# ProPrj_LillyPadPro_2025-09-27.net
KiCad netlist of a schematic drawn in EasyEDA Pro
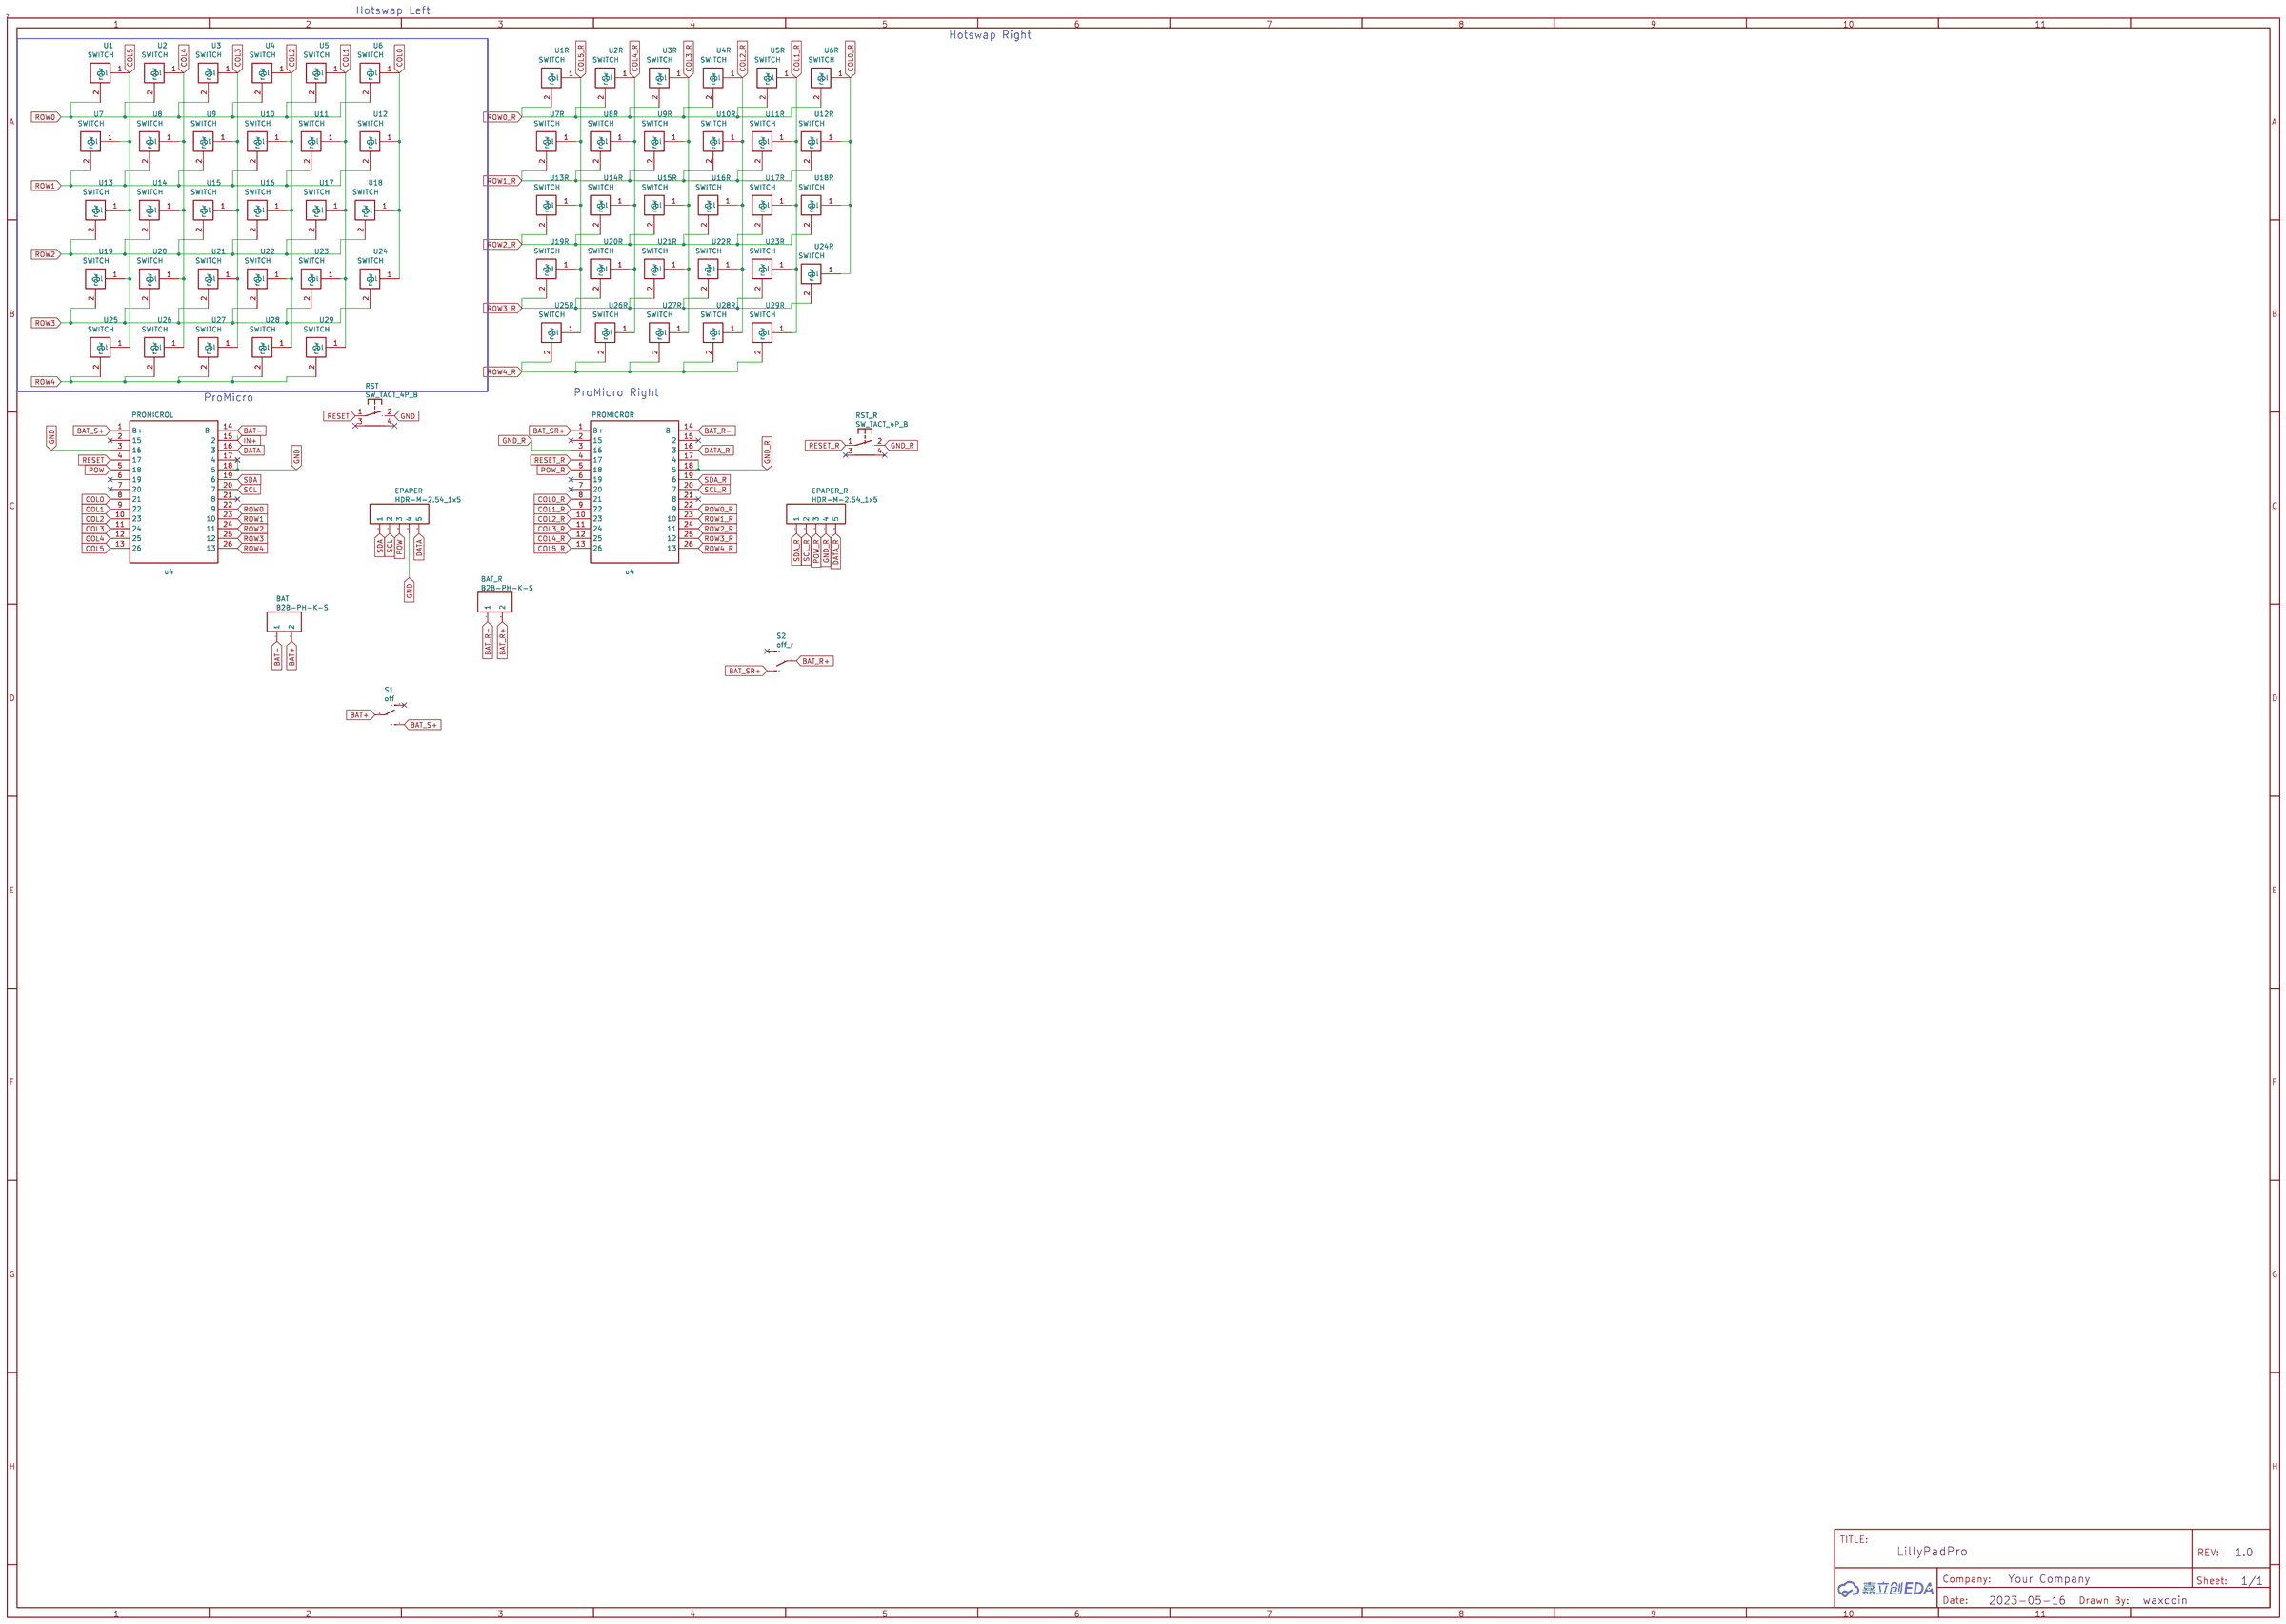
[diagram p0: schematic sheet]

(export (version "E")
  (design (tool "Eeschema 10.0.6"))
  (components
    (comp (ref "BAT")
      (value "B2B-PH-K-S")
      (fields
        (field (name "Manufacturer") "JST Sales America")
        (field (name "Contributor") "single_coil_hum")
      )
      (libsource (lib "easyedapro") (part "B2B-PH-K-S"))
    )
    (comp (ref "BAT_R")
      (value "B2B-PH-K-S")
      (fields
        (field (name "Manufacturer") "JST Sales America")
        (field (name "Contributor") "single_coil_hum")
      )
      (libsource (lib "easyedapro") (part "B2B-PH-K-S"))
    )
    (comp (ref "EPAPER")
      (value "HDR-M-2.54_1x5")
      (fields (field (name "Contributor") "LCEDA_Lib"))
      (libsource (lib "easyedapro") (part "HDR-M-2.54_1x5"))
    )
    (comp (ref "EPAPER_R")
      (value "HDR-M-2.54_1x5")
      (fields (field (name "Contributor") "LCEDA_Lib"))
      (libsource (lib "easyedapro") (part "HDR-M-2.54_1x5"))
    )
    (comp (ref "PROMICROL") (value "u4") (libsource (lib "easyedapro") (part "u4")))
    (comp (ref "PROMICROR") (value "u4") (libsource (lib "easyedapro") (part "u4")))
    (comp (ref "RST")
      (value "SW_TACT_4P_B")
      (fields (field (name "Contributor") "DangerousPrototype"))
      (libsource (lib "easyedapro") (part "SW_TACT_4P_B"))
    )
    (comp (ref "RST_R")
      (value "SW_TACT_4P_B")
      (fields (field (name "Contributor") "DangerousPrototype"))
      (libsource (lib "easyedapro") (part "SW_TACT_4P_B"))
    )
    (comp (ref "S1")
      (value "off")
      (fields (field (name "Contributor") "SparkFun"))
      (libsource (lib "easyedapro") (part "off"))
    )
    (comp (ref "S2")
      (value "off_r")
      (fields (field (name "Contributor") "SparkFun"))
      (libsource (lib "easyedapro") (part "off_r"))
    )
    (comp (ref "U1")
      (value "SWITCH")
      (fields (field (name "Contributor") "angeloger087"))
      (libsource (lib "easyedapro") (part "SWITCH"))
    )
    (comp (ref "U1R")
      (value "SWITCH")
      (fields (field (name "Contributor") "angeloger087"))
      (libsource (lib "easyedapro") (part "SWITCH"))
    )
    (comp (ref "U2")
      (value "SWITCH")
      (fields (field (name "Contributor") "angeloger087"))
      (libsource (lib "easyedapro") (part "SWITCH"))
    )
    (comp (ref "U2R")
      (value "SWITCH")
      (fields (field (name "Contributor") "angeloger087"))
      (libsource (lib "easyedapro") (part "SWITCH"))
    )
    (comp (ref "U3")
      (value "SWITCH")
      (fields (field (name "Contributor") "angeloger087"))
      (libsource (lib "easyedapro") (part "SWITCH"))
    )
    (comp (ref "U3R")
      (value "SWITCH")
      (fields (field (name "Contributor") "angeloger087"))
      (libsource (lib "easyedapro") (part "SWITCH"))
    )
    (comp (ref "U4")
      (value "SWITCH")
      (fields (field (name "Contributor") "angeloger087"))
      (libsource (lib "easyedapro") (part "SWITCH"))
    )
    (comp (ref "U4R")
      (value "SWITCH")
      (fields (field (name "Contributor") "angeloger087"))
      (libsource (lib "easyedapro") (part "SWITCH"))
    )
    (comp (ref "U5")
      (value "SWITCH")
      (fields (field (name "Contributor") "angeloger087"))
      (libsource (lib "easyedapro") (part "SWITCH"))
    )
    (comp (ref "U5R")
      (value "SWITCH")
      (fields (field (name "Contributor") "angeloger087"))
      (libsource (lib "easyedapro") (part "SWITCH"))
    )
    (comp (ref "U6")
      (value "SWITCH")
      (fields (field (name "Contributor") "angeloger087"))
      (libsource (lib "easyedapro") (part "SWITCH"))
    )
    (comp (ref "U6R")
      (value "SWITCH")
      (fields (field (name "Contributor") "angeloger087"))
      (libsource (lib "easyedapro") (part "SWITCH"))
    )
    (comp (ref "U7")
      (value "SWITCH")
      (fields (field (name "Contributor") "angeloger087"))
      (libsource (lib "easyedapro") (part "SWITCH"))
    )
    (comp (ref "U7R")
      (value "SWITCH")
      (fields (field (name "Contributor") "angeloger087"))
      (libsource (lib "easyedapro") (part "SWITCH"))
    )
    (comp (ref "U8")
      (value "SWITCH")
      (fields (field (name "Contributor") "angeloger087"))
      (libsource (lib "easyedapro") (part "SWITCH"))
    )
    (comp (ref "U8R")
      (value "SWITCH")
      (fields (field (name "Contributor") "angeloger087"))
      (libsource (lib "easyedapro") (part "SWITCH"))
    )
    (comp (ref "U9")
      (value "SWITCH")
      (fields (field (name "Contributor") "angeloger087"))
      (libsource (lib "easyedapro") (part "SWITCH"))
    )
    (comp (ref "U9R")
      (value "SWITCH")
      (fields (field (name "Contributor") "angeloger087"))
      (libsource (lib "easyedapro") (part "SWITCH"))
    )
    (comp (ref "U10")
      (value "SWITCH")
      (fields (field (name "Contributor") "angeloger087"))
      (libsource (lib "easyedapro") (part "SWITCH"))
    )
    (comp (ref "U10R")
      (value "SWITCH")
      (fields (field (name "Contributor") "angeloger087"))
      (libsource (lib "easyedapro") (part "SWITCH"))
    )
    (comp (ref "U11")
      (value "SWITCH")
      (fields (field (name "Contributor") "angeloger087"))
      (libsource (lib "easyedapro") (part "SWITCH"))
    )
    (comp (ref "U11R")
      (value "SWITCH")
      (fields (field (name "Contributor") "angeloger087"))
      (libsource (lib "easyedapro") (part "SWITCH"))
    )
    (comp (ref "U12")
      (value "SWITCH")
      (fields (field (name "Contributor") "angeloger087"))
      (libsource (lib "easyedapro") (part "SWITCH"))
    )
    (comp (ref "U12R")
      (value "SWITCH")
      (fields (field (name "Contributor") "angeloger087"))
      (libsource (lib "easyedapro") (part "SWITCH"))
    )
    (comp (ref "U13")
      (value "SWITCH")
      (fields (field (name "Contributor") "angeloger087"))
      (libsource (lib "easyedapro") (part "SWITCH"))
    )
    (comp (ref "U13R")
      (value "SWITCH")
      (fields (field (name "Contributor") "angeloger087"))
      (libsource (lib "easyedapro") (part "SWITCH"))
    )
    (comp (ref "U14")
      (value "SWITCH")
      (fields (field (name "Contributor") "angeloger087"))
      (libsource (lib "easyedapro") (part "SWITCH"))
    )
    (comp (ref "U14R")
      (value "SWITCH")
      (fields (field (name "Contributor") "angeloger087"))
      (libsource (lib "easyedapro") (part "SWITCH"))
    )
    (comp (ref "U15")
      (value "SWITCH")
      (fields (field (name "Contributor") "angeloger087"))
      (libsource (lib "easyedapro") (part "SWITCH"))
    )
    (comp (ref "U15R")
      (value "SWITCH")
      (fields (field (name "Contributor") "angeloger087"))
      (libsource (lib "easyedapro") (part "SWITCH"))
    )
    (comp (ref "U16")
      (value "SWITCH")
      (fields (field (name "Contributor") "angeloger087"))
      (libsource (lib "easyedapro") (part "SWITCH"))
    )
    (comp (ref "U16R")
      (value "SWITCH")
      (fields (field (name "Contributor") "angeloger087"))
      (libsource (lib "easyedapro") (part "SWITCH"))
    )
    (comp (ref "U17")
      (value "SWITCH")
      (fields (field (name "Contributor") "angeloger087"))
      (libsource (lib "easyedapro") (part "SWITCH"))
    )
    (comp (ref "U17R")
      (value "SWITCH")
      (fields (field (name "Contributor") "angeloger087"))
      (libsource (lib "easyedapro") (part "SWITCH"))
    )
    (comp (ref "U18")
      (value "SWITCH")
      (fields (field (name "Contributor") "angeloger087"))
      (libsource (lib "easyedapro") (part "SWITCH"))
    )
    (comp (ref "U18R")
      (value "SWITCH")
      (fields (field (name "Contributor") "angeloger087"))
      (libsource (lib "easyedapro") (part "SWITCH"))
    )
    (comp (ref "U19")
      (value "SWITCH")
      (fields (field (name "Contributor") "angeloger087"))
      (libsource (lib "easyedapro") (part "SWITCH"))
    )
    (comp (ref "U19R")
      (value "SWITCH")
      (fields (field (name "Contributor") "angeloger087"))
      (libsource (lib "easyedapro") (part "SWITCH"))
    )
    (comp (ref "U20")
      (value "SWITCH")
      (fields (field (name "Contributor") "angeloger087"))
      (libsource (lib "easyedapro") (part "SWITCH"))
    )
    (comp (ref "U20R")
      (value "SWITCH")
      (fields (field (name "Contributor") "angeloger087"))
      (libsource (lib "easyedapro") (part "SWITCH"))
    )
    (comp (ref "U21")
      (value "SWITCH")
      (fields (field (name "Contributor") "angeloger087"))
      (libsource (lib "easyedapro") (part "SWITCH"))
    )
    (comp (ref "U21R")
      (value "SWITCH")
      (fields (field (name "Contributor") "angeloger087"))
      (libsource (lib "easyedapro") (part "SWITCH"))
    )
    (comp (ref "U22")
      (value "SWITCH")
      (fields (field (name "Contributor") "angeloger087"))
      (libsource (lib "easyedapro") (part "SWITCH"))
    )
    (comp (ref "U22R")
      (value "SWITCH")
      (fields (field (name "Contributor") "angeloger087"))
      (libsource (lib "easyedapro") (part "SWITCH"))
    )
    (comp (ref "U23")
      (value "SWITCH")
      (fields (field (name "Contributor") "angeloger087"))
      (libsource (lib "easyedapro") (part "SWITCH"))
    )
    (comp (ref "U23R")
      (value "SWITCH")
      (fields (field (name "Contributor") "angeloger087"))
      (libsource (lib "easyedapro") (part "SWITCH"))
    )
    (comp (ref "U24")
      (value "SWITCH")
      (fields (field (name "Contributor") "angeloger087"))
      (libsource (lib "easyedapro") (part "SWITCH"))
    )
    (comp (ref "U24R")
      (value "SWITCH")
      (fields (field (name "Contributor") "angeloger087"))
      (libsource (lib "easyedapro") (part "SWITCH"))
    )
    (comp (ref "U25")
      (value "SWITCH")
      (fields (field (name "Contributor") "angeloger087"))
      (libsource (lib "easyedapro") (part "SWITCH"))
    )
    (comp (ref "U25R")
      (value "SWITCH")
      (fields (field (name "Contributor") "angeloger087"))
      (libsource (lib "easyedapro") (part "SWITCH"))
    )
    (comp (ref "U26")
      (value "SWITCH")
      (fields (field (name "Contributor") "angeloger087"))
      (libsource (lib "easyedapro") (part "SWITCH"))
    )
    (comp (ref "U26R")
      (value "SWITCH")
      (fields (field (name "Contributor") "angeloger087"))
      (libsource (lib "easyedapro") (part "SWITCH"))
    )
    (comp (ref "U27")
      (value "SWITCH")
      (fields (field (name "Contributor") "angeloger087"))
      (libsource (lib "easyedapro") (part "SWITCH"))
    )
    (comp (ref "U27R")
      (value "SWITCH")
      (fields (field (name "Contributor") "angeloger087"))
      (libsource (lib "easyedapro") (part "SWITCH"))
    )
    (comp (ref "U28")
      (value "SWITCH")
      (fields (field (name "Contributor") "angeloger087"))
      (libsource (lib "easyedapro") (part "SWITCH"))
    )
    (comp (ref "U28R")
      (value "SWITCH")
      (fields (field (name "Contributor") "angeloger087"))
      (libsource (lib "easyedapro") (part "SWITCH"))
    )
    (comp (ref "U29")
      (value "SWITCH")
      (fields (field (name "Contributor") "angeloger087"))
      (libsource (lib "easyedapro") (part "SWITCH"))
    )
    (comp (ref "U29R")
      (value "SWITCH")
      (fields (field (name "Contributor") "angeloger087"))
      (libsource (lib "easyedapro") (part "SWITCH"))
    )
  )
  (nets
    (net (code "1") (name "BAT+") (class "Default")
      (node (ref "BAT") (pin "2") (pinfunction "2_2") (pintype "unspecified"))
      (node (ref "S1") (pin "2") (pinfunction "P_2") (pintype "unspecified"))
    )
    (net (code "2") (name "BAT-") (class "Default")
      (node (ref "BAT") (pin "1") (pinfunction "1_1") (pintype "unspecified"))
      (node (ref "PROMICROL") (pin "14") (pinfunction "B-_14") (pintype "unspecified"))
    )
    (net (code "3") (name "BAT_R+") (class "Default")
      (node (ref "BAT_R") (pin "2") (pinfunction "2_2") (pintype "unspecified"))
      (node (ref "S2") (pin "2") (pinfunction "P_2") (pintype "unspecified"))
    )
    (net (code "4") (name "BAT_R-") (class "Default")
      (node (ref "BAT_R") (pin "1") (pinfunction "1_1") (pintype "unspecified"))
      (node (ref "PROMICROR") (pin "14") (pinfunction "B-_14") (pintype "unspecified"))
    )
    (net (code "5") (name "BAT_S+") (class "Default")
      (node (ref "PROMICROL") (pin "1") (pinfunction "B+_1") (pintype "unspecified"))
      (node (ref "S1") (pin "3") (pinfunction "S_3") (pintype "unspecified"))
    )
    (net (code "6") (name "BAT_SR+") (class "Default")
      (node (ref "PROMICROR") (pin "1") (pinfunction "B+_1") (pintype "unspecified"))
      (node (ref "S2") (pin "1") (pinfunction "O_1") (pintype "unspecified"))
    )
    (net (code "7") (name "COL0") (class "Default")
      (node (ref "PROMICROL") (pin "8") (pinfunction "21_8") (pintype "unspecified"))
      (node (ref "U12") (pin "1") (pinfunction "col_1") (pintype "unspecified"))
      (node (ref "U18") (pin "1") (pinfunction "col_1") (pintype "unspecified"))
      (node (ref "U24") (pin "1") (pinfunction "col_1") (pintype "unspecified"))
      (node (ref "U6") (pin "1") (pinfunction "col_1") (pintype "unspecified"))
    )
    (net (code "8") (name "COL0_R") (class "Default")
      (node (ref "PROMICROR") (pin "8") (pinfunction "21_8") (pintype "unspecified"))
      (node (ref "U12R") (pin "1") (pinfunction "col_1") (pintype "unspecified"))
      (node (ref "U18R") (pin "1") (pinfunction "col_1") (pintype "unspecified"))
      (node (ref "U24R") (pin "1") (pinfunction "col_1") (pintype "unspecified"))
      (node (ref "U6R") (pin "1") (pinfunction "col_1") (pintype "unspecified"))
    )
    (net (code "9") (name "COL1") (class "Default")
      (node (ref "PROMICROL") (pin "9") (pinfunction "22_9") (pintype "unspecified"))
      (node (ref "U11") (pin "1") (pinfunction "col_1") (pintype "unspecified"))
      (node (ref "U17") (pin "1") (pinfunction "col_1") (pintype "unspecified"))
      (node (ref "U23") (pin "1") (pinfunction "col_1") (pintype "unspecified"))
      (node (ref "U29") (pin "1") (pinfunction "col_1") (pintype "unspecified"))
      (node (ref "U5") (pin "1") (pinfunction "col_1") (pintype "unspecified"))
    )
    (net (code "10") (name "COL1_R") (class "Default")
      (node (ref "PROMICROR") (pin "9") (pinfunction "22_9") (pintype "unspecified"))
      (node (ref "U11R") (pin "1") (pinfunction "col_1") (pintype "unspecified"))
      (node (ref "U17R") (pin "1") (pinfunction "col_1") (pintype "unspecified"))
      (node (ref "U23R") (pin "1") (pinfunction "col_1") (pintype "unspecified"))
      (node (ref "U29R") (pin "1") (pinfunction "col_1") (pintype "unspecified"))
      (node (ref "U5R") (pin "1") (pinfunction "col_1") (pintype "unspecified"))
    )
    (net (code "11") (name "COL2") (class "Default")
      (node (ref "PROMICROL") (pin "10") (pinfunction "23_10") (pintype "unspecified"))
      (node (ref "U10") (pin "1") (pinfunction "col_1") (pintype "unspecified"))
      (node (ref "U16") (pin "1") (pinfunction "col_1") (pintype "unspecified"))
      (node (ref "U22") (pin "1") (pinfunction "col_1") (pintype "unspecified"))
      (node (ref "U28") (pin "1") (pinfunction "col_1") (pintype "unspecified"))
      (node (ref "U4") (pin "1") (pinfunction "col_1") (pintype "unspecified"))
    )
    (net (code "12") (name "COL2_R") (class "Default")
      (node (ref "PROMICROR") (pin "10") (pinfunction "23_10") (pintype "unspecified"))
      (node (ref "U10R") (pin "1") (pinfunction "col_1") (pintype "unspecified"))
      (node (ref "U16R") (pin "1") (pinfunction "col_1") (pintype "unspecified"))
      (node (ref "U22R") (pin "1") (pinfunction "col_1") (pintype "unspecified"))
      (node (ref "U28R") (pin "1") (pinfunction "col_1") (pintype "unspecified"))
      (node (ref "U4R") (pin "1") (pinfunction "col_1") (pintype "unspecified"))
    )
    (net (code "13") (name "COL3") (class "Default")
      (node (ref "PROMICROL") (pin "11") (pinfunction "24_11") (pintype "unspecified"))
      (node (ref "U15") (pin "1") (pinfunction "col_1") (pintype "unspecified"))
      (node (ref "U21") (pin "1") (pinfunction "col_1") (pintype "unspecified"))
      (node (ref "U27") (pin "1") (pinfunction "col_1") (pintype "unspecified"))
      (node (ref "U3") (pin "1") (pinfunction "col_1") (pintype "unspecified"))
      (node (ref "U9") (pin "1") (pinfunction "col_1") (pintype "unspecified"))
    )
    (net (code "14") (name "COL3_R") (class "Default")
      (node (ref "PROMICROR") (pin "11") (pinfunction "24_11") (pintype "unspecified"))
      (node (ref "U15R") (pin "1") (pinfunction "col_1") (pintype "unspecified"))
      (node (ref "U21R") (pin "1") (pinfunction "col_1") (pintype "unspecified"))
      (node (ref "U27R") (pin "1") (pinfunction "col_1") (pintype "unspecified"))
      (node (ref "U3R") (pin "1") (pinfunction "col_1") (pintype "unspecified"))
      (node (ref "U9R") (pin "1") (pinfunction "col_1") (pintype "unspecified"))
    )
    (net (code "15") (name "COL4") (class "Default")
      (node (ref "PROMICROL") (pin "12") (pinfunction "25_12") (pintype "unspecified"))
      (node (ref "U14") (pin "1") (pinfunction "col_1") (pintype "unspecified"))
      (node (ref "U2") (pin "1") (pinfunction "col_1") (pintype "unspecified"))
      (node (ref "U20") (pin "1") (pinfunction "col_1") (pintype "unspecified"))
      (node (ref "U26") (pin "1") (pinfunction "col_1") (pintype "unspecified"))
      (node (ref "U8") (pin "1") (pinfunction "col_1") (pintype "unspecified"))
    )
    (net (code "16") (name "COL4_R") (class "Default")
      (node (ref "PROMICROR") (pin "12") (pinfunction "25_12") (pintype "unspecified"))
      (node (ref "U14R") (pin "1") (pinfunction "col_1") (pintype "unspecified"))
      (node (ref "U20R") (pin "1") (pinfunction "col_1") (pintype "unspecified"))
      (node (ref "U26R") (pin "1") (pinfunction "col_1") (pintype "unspecified"))
      (node (ref "U2R") (pin "1") (pinfunction "col_1") (pintype "unspecified"))
      (node (ref "U8R") (pin "1") (pinfunction "col_1") (pintype "unspecified"))
    )
    (net (code "17") (name "COL5") (class "Default")
      (node (ref "PROMICROL") (pin "13") (pinfunction "26_13") (pintype "unspecified"))
      (node (ref "U1") (pin "1") (pinfunction "col_1") (pintype "unspecified"))
      (node (ref "U13") (pin "1") (pinfunction "col_1") (pintype "unspecified"))
      (node (ref "U19") (pin "1") (pinfunction "col_1") (pintype "unspecified"))
      (node (ref "U25") (pin "1") (pinfunction "col_1") (pintype "unspecified"))
      (node (ref "U7") (pin "1") (pinfunction "col_1") (pintype "unspecified"))
    )
    (net (code "18") (name "COL5_R") (class "Default")
      (node (ref "PROMICROR") (pin "13") (pinfunction "26_13") (pintype "unspecified"))
      (node (ref "U13R") (pin "1") (pinfunction "col_1") (pintype "unspecified"))
      (node (ref "U19R") (pin "1") (pinfunction "col_1") (pintype "unspecified"))
      (node (ref "U1R") (pin "1") (pinfunction "col_1") (pintype "unspecified"))
      (node (ref "U25R") (pin "1") (pinfunction "col_1") (pintype "unspecified"))
      (node (ref "U7R") (pin "1") (pinfunction "col_1") (pintype "unspecified"))
    )
    (net (code "19") (name "DATA") (class "Default")
      (node (ref "EPAPER") (pin "5") (pinfunction "5_5") (pintype "unspecified"))
      (node (ref "PROMICROL") (pin "16") (pinfunction "3_16") (pintype "unspecified"))
    )
    (net (code "20") (name "DATA_R") (class "Default")
      (node (ref "EPAPER_R") (pin "5") (pinfunction "5_5") (pintype "unspecified"))
      (node (ref "PROMICROR") (pin "16") (pinfunction "3_16") (pintype "unspecified"))
    )
    (net (code "21") (name "GND") (class "Default")
      (node (ref "EPAPER") (pin "4") (pinfunction "4_4") (pintype "unspecified"))
      (node (ref "PROMICROL") (pin "17") (pinfunction "4_17") (pintype "unspecified"))
      (node (ref "PROMICROL") (pin "18") (pinfunction "5_18") (pintype "unspecified"))
      (node (ref "PROMICROL") (pin "3") (pinfunction "16_3") (pintype "unspecified"))
      (node (ref "RST") (pin "2") (pinfunction "2_2") (pintype "unspecified"))
    )
    (net (code "22") (name "GND_R") (class "Default")
      (node (ref "EPAPER_R") (pin "4") (pinfunction "4_4") (pintype "unspecified"))
      (node (ref "PROMICROR") (pin "17") (pinfunction "4_17") (pintype "unspecified"))
      (node (ref "PROMICROR") (pin "18") (pinfunction "5_18") (pintype "unspecified"))
      (node (ref "PROMICROR") (pin "3") (pinfunction "16_3") (pintype "unspecified"))
      (node (ref "RST_R") (pin "2") (pinfunction "2_2") (pintype "unspecified"))
    )
    (net (code "23") (name "IN+") (class "Default")
      (node (ref "PROMICROL") (pin "15") (pinfunction "2_15") (pintype "unspecified"))
    )
    (net (code "24") (name "POW") (class "Default")
      (node (ref "EPAPER") (pin "3") (pinfunction "3_3") (pintype "unspecified"))
      (node (ref "PROMICROL") (pin "5") (pinfunction "18_5") (pintype "unspecified"))
    )
    (net (code "25") (name "POW_R") (class "Default")
      (node (ref "EPAPER_R") (pin "3") (pinfunction "3_3") (pintype "unspecified"))
      (node (ref "PROMICROR") (pin "5") (pinfunction "18_5") (pintype "unspecified"))
    )
    (net (code "26") (name "RESET") (class "Default")
      (node (ref "PROMICROL") (pin "4") (pinfunction "17_4") (pintype "unspecified"))
      (node (ref "RST") (pin "1") (pinfunction "1_1") (pintype "unspecified"))
    )
    (net (code "27") (name "RESET_R") (class "Default")
      (node (ref "PROMICROR") (pin "4") (pinfunction "17_4") (pintype "unspecified"))
      (node (ref "RST_R") (pin "1") (pinfunction "1_1") (pintype "unspecified"))
    )
    (net (code "28") (name "ROW0") (class "Default")
      (node (ref "PROMICROL") (pin "22") (pinfunction "9_22") (pintype "unspecified"))
      (node (ref "U1") (pin "2") (pinfunction "row_2") (pintype "unspecified"))
      (node (ref "U2") (pin "2") (pinfunction "row_2") (pintype "unspecified"))
      (node (ref "U3") (pin "2") (pinfunction "row_2") (pintype "unspecified"))
      (node (ref "U4") (pin "2") (pinfunction "row_2") (pintype "unspecified"))
      (node (ref "U5") (pin "2") (pinfunction "row_2") (pintype "unspecified"))
      (node (ref "U6") (pin "2") (pinfunction "row_2") (pintype "unspecified"))
    )
    (net (code "29") (name "ROW0_R") (class "Default")
      (node (ref "PROMICROR") (pin "22") (pinfunction "9_22") (pintype "unspecified"))
      (node (ref "U1R") (pin "2") (pinfunction "row_2") (pintype "unspecified"))
      (node (ref "U2R") (pin "2") (pinfunction "row_2") (pintype "unspecified"))
      (node (ref "U3R") (pin "2") (pinfunction "row_2") (pintype "unspecified"))
      (node (ref "U4R") (pin "2") (pinfunction "row_2") (pintype "unspecified"))
      (node (ref "U5R") (pin "2") (pinfunction "row_2") (pintype "unspecified"))
      (node (ref "U6R") (pin "2") (pinfunction "row_2") (pintype "unspecified"))
    )
    (net (code "30") (name "ROW1") (class "Default")
      (node (ref "PROMICROL") (pin "23") (pinfunction "10_23") (pintype "unspecified"))
      (node (ref "U10") (pin "2") (pinfunction "row_2") (pintype "unspecified"))
      (node (ref "U11") (pin "2") (pinfunction "row_2") (pintype "unspecified"))
      (node (ref "U12") (pin "2") (pinfunction "row_2") (pintype "unspecified"))
      (node (ref "U7") (pin "2") (pinfunction "row_2") (pintype "unspecified"))
      (node (ref "U8") (pin "2") (pinfunction "row_2") (pintype "unspecified"))
      (node (ref "U9") (pin "2") (pinfunction "row_2") (pintype "unspecified"))
    )
    (net (code "31") (name "ROW1_R") (class "Default")
      (node (ref "PROMICROR") (pin "23") (pinfunction "10_23") (pintype "unspecified"))
      (node (ref "U10R") (pin "2") (pinfunction "row_2") (pintype "unspecified"))
      (node (ref "U11R") (pin "2") (pinfunction "row_2") (pintype "unspecified"))
      (node (ref "U12R") (pin "2") (pinfunction "row_2") (pintype "unspecified"))
      (node (ref "U7R") (pin "2") (pinfunction "row_2") (pintype "unspecified"))
      (node (ref "U8R") (pin "2") (pinfunction "row_2") (pintype "unspecified"))
      (node (ref "U9R") (pin "2") (pinfunction "row_2") (pintype "unspecified"))
    )
    (net (code "32") (name "ROW2") (class "Default")
      (node (ref "PROMICROL") (pin "24") (pinfunction "11_24") (pintype "unspecified"))
      (node (ref "U13") (pin "2") (pinfunction "row_2") (pintype "unspecified"))
      (node (ref "U14") (pin "2") (pinfunction "row_2") (pintype "unspecified"))
      (node (ref "U15") (pin "2") (pinfunction "row_2") (pintype "unspecified"))
      (node (ref "U16") (pin "2") (pinfunction "row_2") (pintype "unspecified"))
      (node (ref "U17") (pin "2") (pinfunction "row_2") (pintype "unspecified"))
      (node (ref "U18") (pin "2") (pinfunction "row_2") (pintype "unspecified"))
    )
    (net (code "33") (name "ROW2_R") (class "Default")
      (node (ref "PROMICROR") (pin "24") (pinfunction "11_24") (pintype "unspecified"))
      (node (ref "U13R") (pin "2") (pinfunction "row_2") (pintype "unspecified"))
      (node (ref "U14R") (pin "2") (pinfunction "row_2") (pintype "unspecified"))
      (node (ref "U15R") (pin "2") (pinfunction "row_2") (pintype "unspecified"))
      (node (ref "U16R") (pin "2") (pinfunction "row_2") (pintype "unspecified"))
      (node (ref "U17R") (pin "2") (pinfunction "row_2") (pintype "unspecified"))
      (node (ref "U18R") (pin "2") (pinfunction "row_2") (pintype "unspecified"))
    )
    (net (code "34") (name "ROW3") (class "Default")
      (node (ref "PROMICROL") (pin "25") (pinfunction "12_25") (pintype "unspecified"))
      (node (ref "U19") (pin "2") (pinfunction "row_2") (pintype "unspecified"))
      (node (ref "U20") (pin "2") (pinfunction "row_2") (pintype "unspecified"))
      (node (ref "U21") (pin "2") (pinfunction "row_2") (pintype "unspecified"))
      (node (ref "U22") (pin "2") (pinfunction "row_2") (pintype "unspecified"))
      (node (ref "U23") (pin "2") (pinfunction "row_2") (pintype "unspecified"))
      (node (ref "U24") (pin "2") (pinfunction "row_2") (pintype "unspecified"))
    )
    (net (code "35") (name "ROW3_R") (class "Default")
      (node (ref "PROMICROR") (pin "25") (pinfunction "12_25") (pintype "unspecified"))
      (node (ref "U19R") (pin "2") (pinfunction "row_2") (pintype "unspecified"))
      (node (ref "U20R") (pin "2") (pinfunction "row_2") (pintype "unspecified"))
      (node (ref "U21R") (pin "2") (pinfunction "row_2") (pintype "unspecified"))
      (node (ref "U22R") (pin "2") (pinfunction "row_2") (pintype "unspecified"))
      (node (ref "U23R") (pin "2") (pinfunction "row_2") (pintype "unspecified"))
      (node (ref "U24R") (pin "2") (pinfunction "row_2") (pintype "unspecified"))
    )
    (net (code "36") (name "ROW4") (class "Default")
      (node (ref "PROMICROL") (pin "26") (pinfunction "13_26") (pintype "unspecified"))
      (node (ref "U25") (pin "2") (pinfunction "row_2") (pintype "unspecified"))
      (node (ref "U26") (pin "2") (pinfunction "row_2") (pintype "unspecified"))
      (node (ref "U27") (pin "2") (pinfunction "row_2") (pintype "unspecified"))
      (node (ref "U28") (pin "2") (pinfunction "row_2") (pintype "unspecified"))
      (node (ref "U29") (pin "2") (pinfunction "row_2") (pintype "unspecified"))
    )
    (net (code "37") (name "ROW4_R") (class "Default")
      (node (ref "PROMICROR") (pin "26") (pinfunction "13_26") (pintype "unspecified"))
      (node (ref "U25R") (pin "2") (pinfunction "row_2") (pintype "unspecified"))
      (node (ref "U26R") (pin "2") (pinfunction "row_2") (pintype "unspecified"))
      (node (ref "U27R") (pin "2") (pinfunction "row_2") (pintype "unspecified"))
      (node (ref "U28R") (pin "2") (pinfunction "row_2") (pintype "unspecified"))
      (node (ref "U29R") (pin "2") (pinfunction "row_2") (pintype "unspecified"))
    )
    (net (code "38") (name "SCL") (class "Default")
      (node (ref "EPAPER") (pin "2") (pinfunction "2_2") (pintype "unspecified"))
      (node (ref "PROMICROL") (pin "20") (pinfunction "7_20") (pintype "unspecified"))
    )
    (net (code "39") (name "SCL_R") (class "Default")
      (node (ref "EPAPER_R") (pin "2") (pinfunction "2_2") (pintype "unspecified"))
      (node (ref "PROMICROR") (pin "20") (pinfunction "7_20") (pintype "unspecified"))
    )
    (net (code "40") (name "SDA") (class "Default")
      (node (ref "EPAPER") (pin "1") (pinfunction "1_1") (pintype "unspecified"))
      (node (ref "PROMICROL") (pin "19") (pinfunction "6_19") (pintype "unspecified"))
    )
    (net (code "41") (name "SDA_R") (class "Default")
      (node (ref "EPAPER_R") (pin "1") (pinfunction "1_1") (pintype "unspecified"))
      (node (ref "PROMICROR") (pin "19") (pinfunction "6_19") (pintype "unspecified"))
    )
    (net (code "42") (name "unconnected-(PROMICROL-8-Pad21)") (class "Default")
      (node (ref "PROMICROL") (pin "21") (pinfunction "8_21") (pintype "unspecified+no_connect"))
    )
    (net (code "43") (name "unconnected-(PROMICROL-15-Pad2)") (class "Default")
      (node (ref "PROMICROL") (pin "2") (pinfunction "15_2") (pintype "unspecified+no_connect"))
    )
    (net (code "44") (name "unconnected-(PROMICROL-19-Pad6)") (class "Default")
      (node (ref "PROMICROL") (pin "6") (pinfunction "19_6") (pintype "unspecified+no_connect"))
    )
    (net (code "45") (name "unconnected-(PROMICROL-20-Pad7)") (class "Default")
      (node (ref "PROMICROL") (pin "7") (pinfunction "20_7") (pintype "unspecified+no_connect"))
    )
    (net (code "46") (name "unconnected-(PROMICROR-2-Pad15)") (class "Default")
      (node (ref "PROMICROR") (pin "15") (pinfunction "2_15") (pintype "unspecified+no_connect"))
    )
    (net (code "47") (name "unconnected-(PROMICROR-8-Pad21)") (class "Default")
      (node (ref "PROMICROR") (pin "21") (pinfunction "8_21") (pintype "unspecified+no_connect"))
    )
    (net (code "48") (name "unconnected-(PROMICROR-15-Pad2)") (class "Default")
      (node (ref "PROMICROR") (pin "2") (pinfunction "15_2") (pintype "unspecified+no_connect"))
    )
    (net (code "49") (name "unconnected-(PROMICROR-19-Pad6)") (class "Default")
      (node (ref "PROMICROR") (pin "6") (pinfunction "19_6") (pintype "unspecified+no_connect"))
    )
    (net (code "50") (name "unconnected-(PROMICROR-20-Pad7)") (class "Default")
      (node (ref "PROMICROR") (pin "7") (pinfunction "20_7") (pintype "unspecified+no_connect"))
    )
    (net (code "51") (name "unconnected-(RST-Pad3)") (class "Default")
      (node (ref "RST") (pin "3") (pinfunction "3_3") (pintype "unspecified+no_connect"))
    )
    (net (code "52") (name "unconnected-(RST-Pad4)") (class "Default")
      (node (ref "RST") (pin "4") (pinfunction "4_4") (pintype "unspecified+no_connect"))
    )
    (net (code "53") (name "unconnected-(RST_R-Pad3)") (class "Default")
      (node (ref "RST_R") (pin "3") (pinfunction "3_3") (pintype "unspecified+no_connect"))
    )
    (net (code "54") (name "unconnected-(RST_R-Pad4)") (class "Default")
      (node (ref "RST_R") (pin "4") (pinfunction "4_4") (pintype "unspecified+no_connect"))
    )
    (net (code "55") (name "unconnected-(S1-O-Pad1)") (class "Default")
      (node (ref "S1") (pin "1") (pinfunction "O_1") (pintype "unspecified+no_connect"))
    )
    (net (code "56") (name "unconnected-(S2-S-Pad3)") (class "Default")
      (node (ref "S2") (pin "3") (pinfunction "S_3") (pintype "unspecified+no_connect"))
    )
  )
)
